# lab_1_somov_usb_i2c.net
KiCad netlist of a schematic drawn in Altium Designer
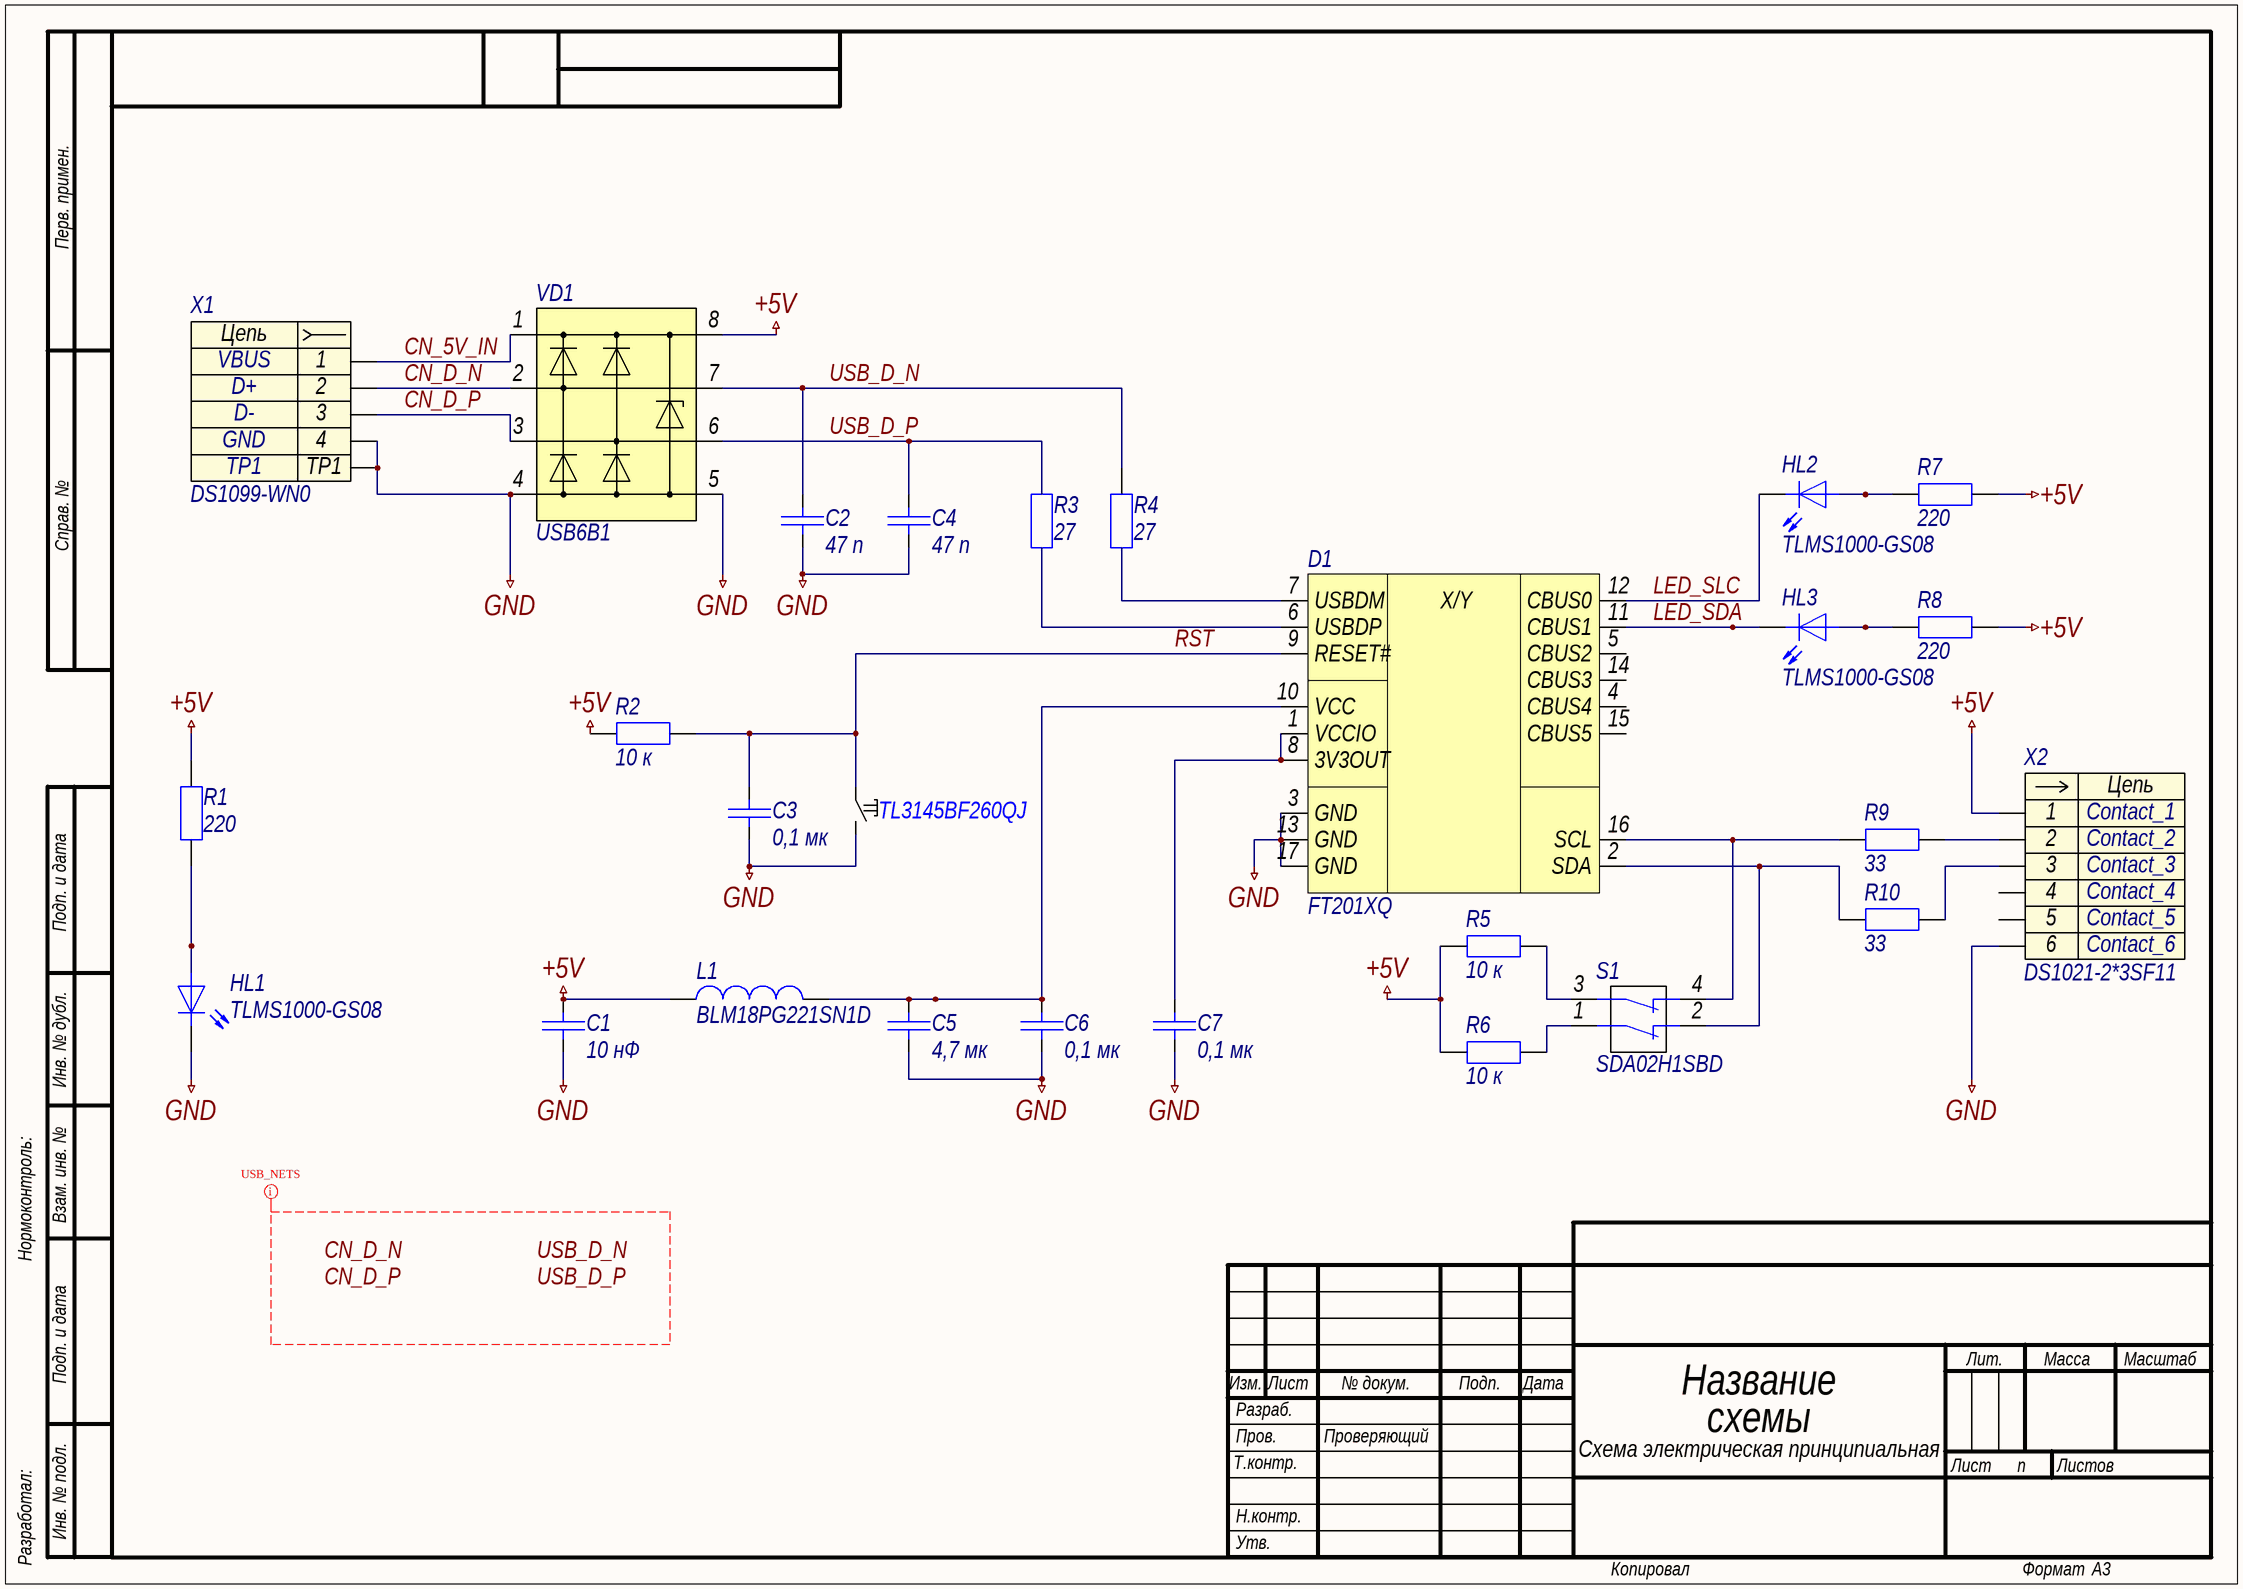
[diagram p0: lab_1_somov_usb_i2c.SchDoc]

(export (version "E")
  (design (tool "Eeschema 10.0.6"))
  (components
    (comp (ref "C1")
      (value "10 нФ")
      (footprint "C0402")
      (description "=Описание")
      (libsource (lib "Database_Students") (part "C-NONPOLAR"))
    )
    (comp (ref "C2")
      (value "47 п")
      (footprint "C0201")
      (description "=Описание")
      (libsource (lib "Database_Students") (part "C-NONPOLAR"))
    )
    (comp (ref "C3")
      (value "0,1 мк")
      (footprint "C0603")
      (description "=Описание")
      (libsource (lib "Database_Students") (part "C-NONPOLAR"))
    )
    (comp (ref "C4")
      (value "47 п")
      (footprint "C0201")
      (description "=Описание")
      (libsource (lib "Database_Students") (part "C-NONPOLAR"))
    )
    (comp (ref "C5")
      (value "4,7 мк")
      (footprint "C0603")
      (description "=Описание")
      (libsource (lib "Database_Students") (part "C-NONPOLAR"))
    )
    (comp (ref "C6")
      (value "0,1 мк")
      (footprint "C0603")
      (description "=Описание")
      (libsource (lib "Database_Students") (part "C-NONPOLAR"))
    )
    (comp (ref "C7")
      (value "0,1 мк")
      (footprint "C0603")
      (description "=Описание")
      (libsource (lib "Database_Students") (part "C-NONPOLAR"))
    )
    (comp (ref "D1") (value "FT201XQ") (footprint "FT201XQ") (libsource (lib "Schlib1") (part "FT201XQ")))
    (comp (ref "HL1")
      (value "TLMS1000-GS08")
      (footprint "HL0603")
      (description "=Описание")
      (libsource (lib "Database_Students") (part "HL-COMMON"))
    )
    (comp (ref "HL2")
      (value "TLMS1000-GS08")
      (footprint "HL0603")
      (description "=Описание")
      (libsource (lib "Database_Students") (part "HL-COMMON"))
    )
    (comp (ref "HL3")
      (value "TLMS1000-GS08")
      (footprint "HL0603")
      (description "=Описание")
      (libsource (lib "Database_Students") (part "HL-COMMON"))
    )
    (comp (ref "L1")
      (value "BLM18PG221SN1D")
      (footprint "BLM-2-0603")
      (description "=Описание")
      (libsource (lib "Database_Students") (part "FERRITE-BEAD"))
    )
    (comp (ref "R1")
      (value "220")
      (footprint "R0603")
      (description "=Описание")
      (libsource (lib "Database_Students") (part "R-COMMON"))
    )
    (comp (ref "R2")
      (value "10 к")
      (footprint "R0603")
      (description "=Описание")
      (libsource (lib "Database_Students") (part "R-COMMON"))
    )
    (comp (ref "R3") (value "27") (footprint "R27") (libsource (lib "Schlib2") (part "R27")))
    (comp (ref "R4") (value "27") (footprint "R27") (libsource (lib "Schlib2") (part "R27")))
    (comp (ref "R5")
      (value "10 к")
      (footprint "R0603")
      (description "=Описание")
      (libsource (lib "Database_Students") (part "R-COMMON"))
    )
    (comp (ref "R6")
      (value "10 к")
      (footprint "R0603")
      (description "=Описание")
      (libsource (lib "Database_Students") (part "R-COMMON"))
    )
    (comp (ref "R7")
      (value "220")
      (footprint "R0603")
      (description "=Описание")
      (libsource (lib "Database_Students") (part "R-COMMON"))
    )
    (comp (ref "R8")
      (value "220")
      (footprint "R0603")
      (description "=Описание")
      (libsource (lib "Database_Students") (part "R-COMMON"))
    )
    (comp (ref "R9")
      (value "33")
      (footprint "R0603")
      (description "=Описание")
      (libsource (lib "Database_Students") (part "R-COMMON"))
    )
    (comp (ref "R10")
      (value "33")
      (footprint "R0603")
      (description "=Описание")
      (libsource (lib "Database_Students") (part "R-COMMON"))
    )
    (comp (ref "S1")
      (value "SDA02H1SBD")
      (footprint "DIP-SWITCH-02-706X930X545")
      (description "=Описание")
      (libsource (lib "Database_Students") (part "SWITCH-02"))
    )
    (comp (ref "TL3145BF260QJ")
      (value "~")
      (footprint "BUT: 3x4x2 SMT")
      (description "SMT 3*4*2 2PIN")
      (fields
        (field (name "MANUFACTURER") "xin cheng electronic")
        (field (name "VALUEMANUFACTURERPARTNUMBER") ", 3*4*2mm")
      )
      (libsource (lib "electromechanics") (part "Button_3x4x2_SMT"))
    )
    (comp (ref "VD1")
      (value "USB6B1")
      (footprint "SO-8")
      (description "=Описание")
      (libsource (lib "Database_Students") (part "USB6B1"))
    )
    (comp (ref "X1")
      (value "DS1099-WN0")
      (footprint "DS1099-WN0")
      (description "=Описание")
      (libsource (lib "Database_Students") (part "HEADER-4-TP1-SCT"))
    )
    (comp (ref "X2")
      (value "DS1021-2*3SF11")
      (footprint "DS1021-2X3SF11")
      (description "=Описание")
      (libsource (lib "Database_Students") (part "HEADER-6-PLG"))
    )
  )
  (nets
    (net (code "1") (name "+5V") (class "Default")
      (node (ref "C1") (pin "1") (pinfunction "1_1") (pintype "passive"))
      (node (ref "L1") (pin "1") (pinfunction "1_1") (pintype "passive"))
      (node (ref "R1") (pin "2") (pinfunction "2_2") (pintype "passive"))
      (node (ref "R2") (pin "1") (pinfunction "1_1") (pintype "passive"))
      (node (ref "R5") (pin "1") (pinfunction "1_1") (pintype "passive"))
      (node (ref "R6") (pin "1") (pinfunction "1_1") (pintype "passive"))
      (node (ref "R7") (pin "2") (pinfunction "2_2") (pintype "passive"))
      (node (ref "R8") (pin "2") (pinfunction "2_2") (pintype "passive"))
      (node (ref "VD1") (pin "8") (pinfunction "8_8") (pintype "passive"))
      (node (ref "X2") (pin "1") (pinfunction "1_1") (pintype "passive"))
    )
    (net (code "2") (name "/CN_5V_IN") (class "Default")
      (node (ref "VD1") (pin "1") (pinfunction "1_1") (pintype "passive"))
      (node (ref "X1") (pin "1") (pinfunction "1_1") (pintype "passive"))
    )
    (net (code "3") (name "/CN_D_N") (class "Default")
      (node (ref "VD1") (pin "2") (pinfunction "2_2") (pintype "passive"))
      (node (ref "X1") (pin "2") (pinfunction "2_2") (pintype "passive"))
    )
    (net (code "4") (name "/CN_D_P") (class "Default")
      (node (ref "VD1") (pin "3") (pinfunction "3_3") (pintype "passive"))
      (node (ref "X1") (pin "3") (pinfunction "3_3") (pintype "passive"))
    )
    (net (code "5") (name "/LED_SDA") (class "Default")
      (node (ref "D1") (pin "11") (pinfunction "CBUS1_11") (pintype "passive"))
      (node (ref "HL3") (pin "1") (pinfunction "1_1") (pintype "passive"))
    )
    (net (code "6") (name "/LED_SLC") (class "Default")
      (node (ref "D1") (pin "12") (pinfunction "CBUS0_12") (pintype "passive"))
      (node (ref "HL2") (pin "1") (pinfunction "1_1") (pintype "passive"))
    )
    (net (code "7") (name "/RST") (class "Default")
      (node (ref "C3") (pin "1") (pinfunction "1_1") (pintype "passive"))
      (node (ref "D1") (pin "9") (pinfunction "RESET#_9") (pintype "passive"))
      (node (ref "R2") (pin "2") (pinfunction "2_2") (pintype "passive"))
      (node (ref "TL3145BF260QJ") (pin "1") (pinfunction "1_1") (pintype "passive"))
    )
    (net (code "8") (name "/USB_D_N") (class "Default")
      (node (ref "C2") (pin "1") (pinfunction "1_1") (pintype "passive"))
      (node (ref "VD1") (pin "7") (pinfunction "7_7") (pintype "passive"))
    )
    (net (code "9") (name "/USB_D_P") (class "Default")
      (node (ref "C4") (pin "1") (pinfunction "1_1") (pintype "passive"))
      (node (ref "R3") (pin "2") (pinfunction "2_2") (pintype "passive"))
      (node (ref "VD1") (pin "6") (pinfunction "6_6") (pintype "passive"))
    )
    (net (code "10") (name "GND") (class "Default")
      (node (ref "C1") (pin "2") (pinfunction "2_2") (pintype "passive"))
      (node (ref "C2") (pin "2") (pinfunction "2_2") (pintype "passive"))
      (node (ref "C3") (pin "2") (pinfunction "2_2") (pintype "passive"))
      (node (ref "C4") (pin "2") (pinfunction "2_2") (pintype "passive"))
      (node (ref "C5") (pin "2") (pinfunction "2_2") (pintype "passive"))
      (node (ref "C6") (pin "2") (pinfunction "2_2") (pintype "passive"))
      (node (ref "C7") (pin "2") (pinfunction "2_2") (pintype "passive"))
      (node (ref "D1") (pin "13") (pinfunction "GND_13") (pintype "passive"))
      (node (ref "D1") (pin "17") (pinfunction "GND_17") (pintype "passive"))
      (node (ref "D1") (pin "3") (pinfunction "GND_3") (pintype "passive"))
      (node (ref "HL1") (pin "1") (pinfunction "1_1") (pintype "passive"))
      (node (ref "TL3145BF260QJ") (pin "2") (pinfunction "2_2") (pintype "passive"))
      (node (ref "VD1") (pin "4") (pinfunction "4_4") (pintype "passive"))
      (node (ref "VD1") (pin "5") (pinfunction "5_5") (pintype "passive"))
      (node (ref "X1") (pin "4") (pinfunction "4_4") (pintype "passive"))
      (node (ref "X1") (pin "TP1") (pinfunction "TP1_TP1") (pintype "passive"))
      (node (ref "X2") (pin "6") (pinfunction "6_6") (pintype "passive"))
    )
    (net (code "11") (name "Net-(D1-3V3OUT)") (class "Default")
      (node (ref "C7") (pin "1") (pinfunction "1_1") (pintype "passive"))
      (node (ref "D1") (pin "1") (pinfunction "VCCIO_1") (pintype "passive"))
      (node (ref "D1") (pin "8") (pinfunction "3V3OUT_8") (pintype "passive"))
    )
    (net (code "12") (name "Net-(D1-SCL)") (class "Default")
      (node (ref "D1") (pin "16") (pinfunction "SCL_16") (pintype "passive"))
      (node (ref "R9") (pin "1") (pinfunction "1_1") (pintype "passive"))
      (node (ref "S1") (pin "4") (pinfunction "4_4") (pintype "passive"))
    )
    (net (code "13") (name "Net-(D1-SDA)") (class "Default")
      (node (ref "D1") (pin "2") (pinfunction "SDA_2") (pintype "passive"))
      (node (ref "R10") (pin "1") (pinfunction "1_1") (pintype "passive"))
      (node (ref "S1") (pin "2") (pinfunction "2_2") (pintype "passive"))
    )
    (net (code "14") (name "Net-(D1-USBDM)") (class "Default")
      (node (ref "D1") (pin "7") (pinfunction "USBDM_7") (pintype "passive"))
      (node (ref "R4") (pin "1") (pinfunction "1_1") (pintype "passive"))
    )
    (net (code "15") (name "Net-(D1-USBDP)") (class "Default")
      (node (ref "D1") (pin "6") (pinfunction "USBDP_6") (pintype "passive"))
      (node (ref "R3") (pin "1") (pinfunction "1_1") (pintype "passive"))
    )
    (net (code "16") (name "Net-(D1-VCC)") (class "Default")
      (node (ref "C5") (pin "1") (pinfunction "1_1") (pintype "passive"))
      (node (ref "C6") (pin "1") (pinfunction "1_1") (pintype "passive"))
      (node (ref "D1") (pin "10") (pinfunction "VCC_10") (pintype "passive"))
      (node (ref "L1") (pin "2") (pinfunction "2_2") (pintype "passive"))
    )
    (net (code "17") (name "Net-(HL1-Pad2)") (class "Default")
      (node (ref "HL1") (pin "2") (pinfunction "2_2") (pintype "passive"))
      (node (ref "R1") (pin "1") (pinfunction "1_1") (pintype "passive"))
    )
    (net (code "18") (name "Net-(HL2-Pad2)") (class "Default")
      (node (ref "HL2") (pin "2") (pinfunction "2_2") (pintype "passive"))
      (node (ref "R7") (pin "1") (pinfunction "1_1") (pintype "passive"))
    )
    (net (code "19") (name "Net-(HL3-Pad2)") (class "Default")
      (node (ref "HL3") (pin "2") (pinfunction "2_2") (pintype "passive"))
      (node (ref "R8") (pin "1") (pinfunction "1_1") (pintype "passive"))
    )
    (net (code "20") (name "Net-(R5-Pad2)") (class "Default")
      (node (ref "R5") (pin "2") (pinfunction "2_2") (pintype "passive"))
      (node (ref "S1") (pin "3") (pinfunction "3_3") (pintype "passive"))
    )
    (net (code "21") (name "Net-(R6-Pad2)") (class "Default")
      (node (ref "R6") (pin "2") (pinfunction "2_2") (pintype "passive"))
      (node (ref "S1") (pin "1") (pinfunction "1_1") (pintype "passive"))
    )
    (net (code "22") (name "Net-(R9-Pad2)") (class "Default")
      (node (ref "R9") (pin "2") (pinfunction "2_2") (pintype "passive"))
      (node (ref "X2") (pin "2") (pinfunction "2_2") (pintype "passive"))
    )
    (net (code "23") (name "Net-(R10-Pad2)") (class "Default")
      (node (ref "R10") (pin "2") (pinfunction "2_2") (pintype "passive"))
      (node (ref "X2") (pin "3") (pinfunction "3_3") (pintype "passive"))
    )
    (net (code "24") (name "unconnected-(D1-CBUS2-Pad5)") (class "Default")
      (node (ref "D1") (pin "5") (pinfunction "CBUS2_5") (pintype "passive"))
    )
    (net (code "25") (name "unconnected-(D1-CBUS3-Pad14)") (class "Default")
      (node (ref "D1") (pin "14") (pinfunction "CBUS3_14") (pintype "passive"))
    )
    (net (code "26") (name "unconnected-(D1-CBUS4-Pad4)") (class "Default")
      (node (ref "D1") (pin "4") (pinfunction "CBUS4_4") (pintype "passive"))
    )
    (net (code "27") (name "unconnected-(D1-CBUS5-Pad15)") (class "Default")
      (node (ref "D1") (pin "15") (pinfunction "CBUS5_15") (pintype "passive"))
    )
    (net (code "28") (name "unconnected-(R4-Pad2)") (class "Default")
      (node (ref "R4") (pin "2") (pinfunction "2_2") (pintype "passive"))
    )
    (net (code "29") (name "unconnected-(X2-Pad4)") (class "Default")
      (node (ref "X2") (pin "4") (pinfunction "4_4") (pintype "passive"))
    )
    (net (code "30") (name "unconnected-(X2-Pad5)") (class "Default")
      (node (ref "X2") (pin "5") (pinfunction "5_5") (pintype "passive"))
    )
  )
)
